# meanwell-irm.net
KiCad netlist of a schematic drawn in EAGLE
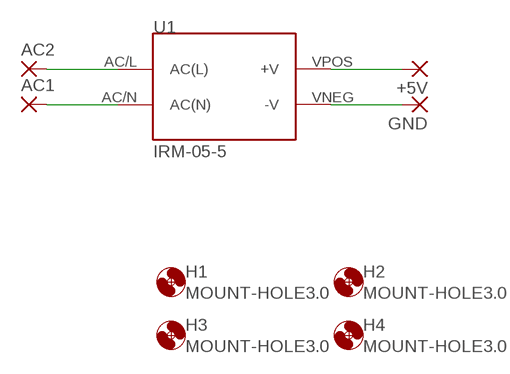
[diagram p0: schematic, sheet 1]

(export (version "E")
  (design (tool "Eeschema 10.0.6"))
  (components
    (comp (ref "+5V")
      (value "3,81/1,4")
      (footprint "eagle-import:3,81_1,4")
      (libsource (lib "eagle-import") (part "3,81/1,4"))
    )
    (comp (ref "AC1")
      (value "3,81/1,4")
      (footprint "eagle-import:3,81_1,4")
      (libsource (lib "eagle-import") (part "3,81/1,4"))
    )
    (comp (ref "AC2")
      (value "3,81/1,4")
      (footprint "eagle-import:3,81_1,4")
      (libsource (lib "eagle-import") (part "3,81/1,4"))
    )
    (comp (ref "GND")
      (value "3,81/1,4")
      (footprint "eagle-import:3,81_1,4")
      (libsource (lib "eagle-import") (part "3,81/1,4"))
    )
    (comp (ref "H1")
      (value "MOUNT-HOLE3.0")
      (footprint "eagle-import:3,0")
      (libsource (lib "eagle-import") (part "MOUNT-HOLE3.0"))
    )
    (comp (ref "H2")
      (value "MOUNT-HOLE3.0")
      (footprint "eagle-import:3,0")
      (libsource (lib "eagle-import") (part "MOUNT-HOLE3.0"))
    )
    (comp (ref "H3")
      (value "MOUNT-HOLE3.0")
      (footprint "eagle-import:3,0")
      (libsource (lib "eagle-import") (part "MOUNT-HOLE3.0"))
    )
    (comp (ref "H4")
      (value "MOUNT-HOLE3.0")
      (footprint "eagle-import:3,0")
      (libsource (lib "eagle-import") (part "MOUNT-HOLE3.0"))
    )
    (comp (ref "U1")
      (value "IRM-05-5")
      (footprint "eagle-import:CONV_IRM-05-5")
      (fields (field (name "MF") "MEAN WELL"))
      (libsource (lib "eagle-import") (part "IRM-05-5"))
    )
  )
  (nets
    (net (code "1") (name "Net-(+5V-P)") (class "Default")
      (node (ref "+5V") (pin "1") (pinfunction "P_1") (pintype "passive"))
      (node (ref "U1") (pin "VPOS") (pinfunction "+V_VPOS") (pintype "output"))
    )
    (net (code "2") (name "Net-(AC1-P)") (class "Default")
      (node (ref "AC1") (pin "1") (pinfunction "P_1") (pintype "passive"))
      (node (ref "U1") (pin "AC/N") (pinfunction "AC(N)_AC/N") (pintype "input"))
    )
    (net (code "3") (name "Net-(AC2-P)") (class "Default")
      (node (ref "AC2") (pin "1") (pinfunction "P_1") (pintype "passive"))
      (node (ref "U1") (pin "AC/L") (pinfunction "AC(L)_AC/L") (pintype "input"))
    )
    (net (code "4") (name "Net-(GND-P)") (class "Default")
      (node (ref "GND") (pin "1") (pinfunction "P_1") (pintype "passive"))
      (node (ref "U1") (pin "VNEG") (pinfunction "-V_VNEG") (pintype "output"))
    )
  )
)
